# MySensors_D1_mini.net
KiCad netlist of a schematic drawn in EAGLE
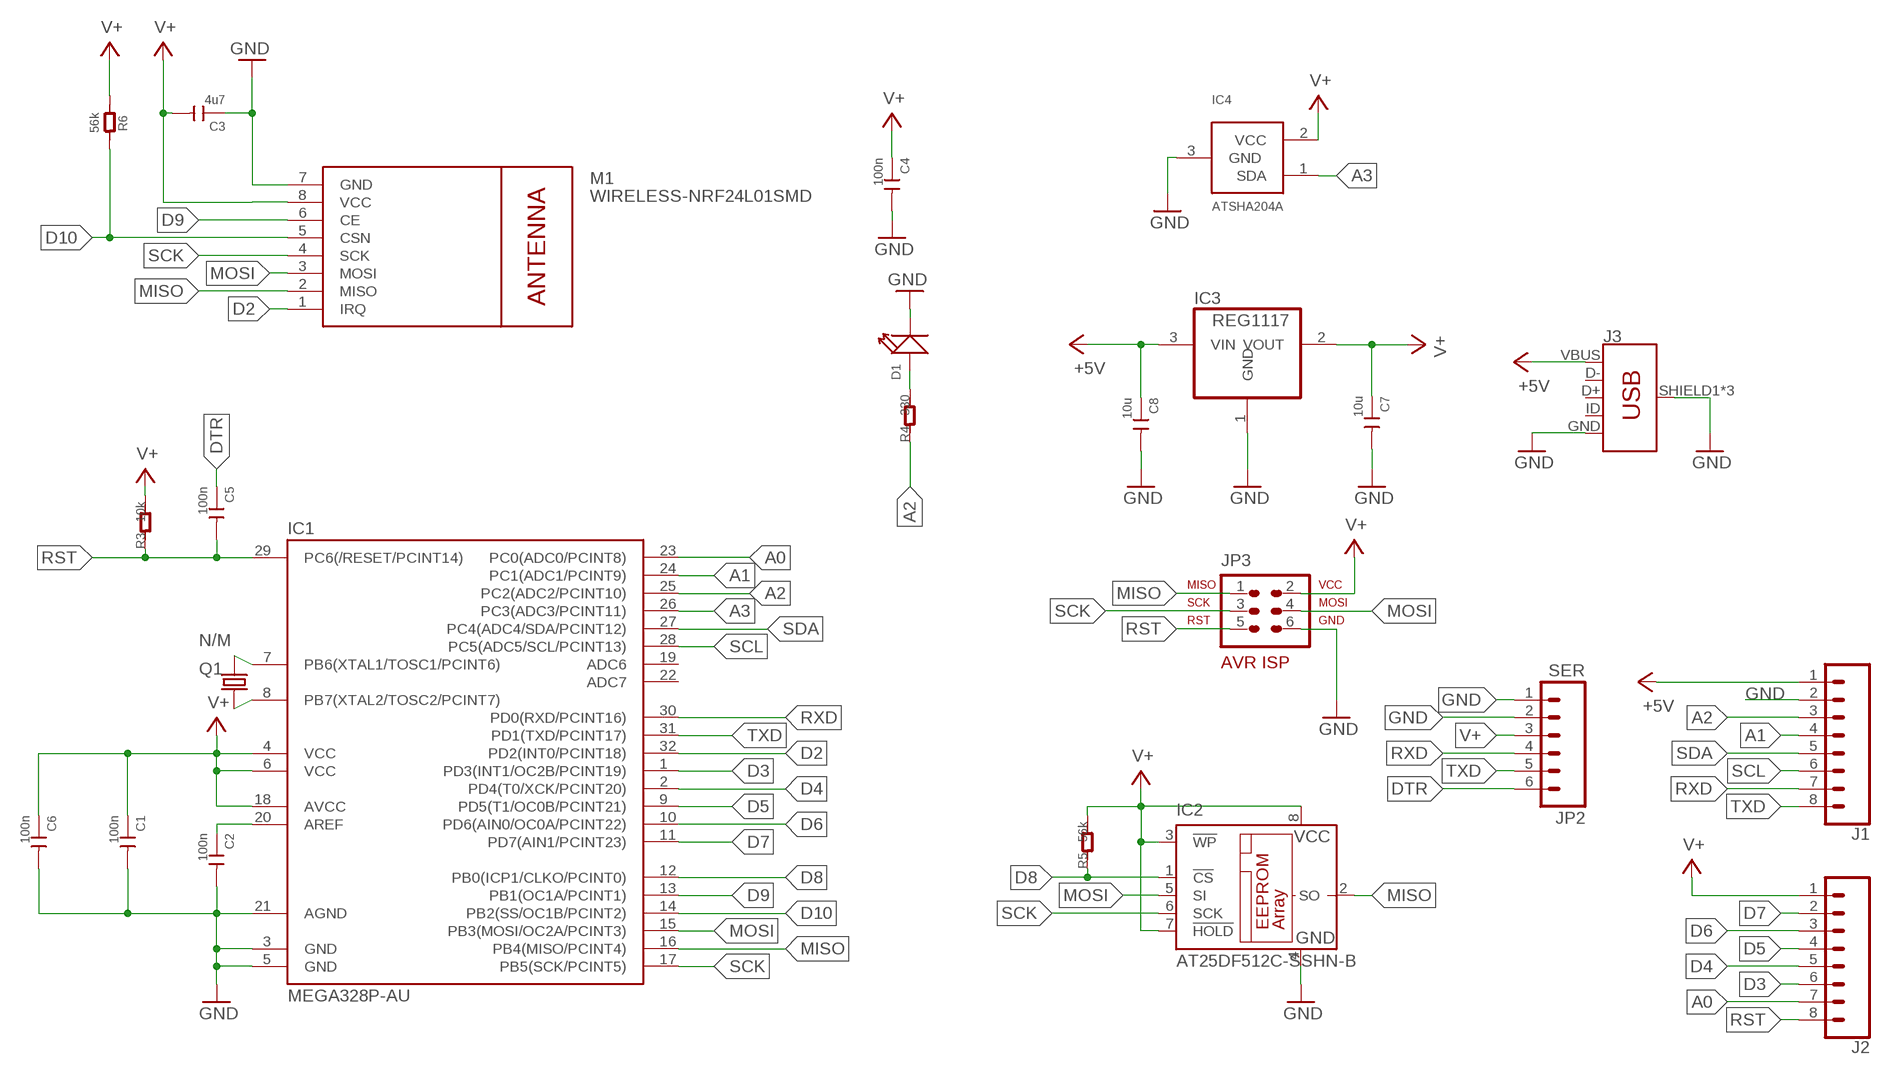
[diagram p0: schematic, sheet 1]

(export (version "E")
  (design (tool "Eeschema 10.0.6"))
  (components
    (comp (ref "C1")
      (value "100n")
      (footprint "eagle-import:C0402")
      (libsource (lib "eagle-import") (part "CAP-0402"))
    )
    (comp (ref "C2")
      (value "100n")
      (footprint "eagle-import:C0402")
      (libsource (lib "eagle-import") (part "CAP-0402"))
    )
    (comp (ref "C3")
      (value "4u7")
      (footprint "eagle-import:C0603")
      (libsource (lib "eagle-import") (part "CAP-0603"))
    )
    (comp (ref "C4")
      (value "100n")
      (footprint "eagle-import:C0402")
      (libsource (lib "eagle-import") (part "CAP-0402"))
    )
    (comp (ref "C5")
      (value "100n")
      (footprint "eagle-import:C0402")
      (libsource (lib "eagle-import") (part "CAP-0402"))
    )
    (comp (ref "C6")
      (value "100n")
      (footprint "eagle-import:C0402")
      (libsource (lib "eagle-import") (part "CAP-0402"))
    )
    (comp (ref "C7")
      (value "10u")
      (footprint "eagle-import:C1206")
      (libsource (lib "eagle-import") (part "CAP-1206"))
    )
    (comp (ref "C8")
      (value "10u")
      (footprint "eagle-import:C1206")
      (libsource (lib "eagle-import") (part "CAP-1206"))
    )
    (comp (ref "D1")
      (value "LED-0402")
      (footprint "eagle-import:LED-0402")
      (libsource (lib "eagle-import") (part "LED-0402"))
    )
    (comp (ref "IC1")
      (value "MEGA328P-AU")
      (footprint "eagle-import:TQFP32-08")
      (libsource (lib "eagle-import") (part "MEGA48/88/168-AU"))
    )
    (comp (ref "IC2")
      (value "AT25DF512C-SSHN-B")
      (footprint "eagle-import:SO-08")
      (fields (field (name "MF") "MICROCHIP") (field (name "MPN") "25AA080/SN"))
      (libsource (lib "eagle-import") (part "25SNAA080"))
    )
    (comp (ref "IC3")
      (value "REG1117")
      (footprint "eagle-import:SOT223")
      (libsource (lib "eagle-import") (part "REG1117"))
    )
    (comp (ref "IC4")
      (value "ATSHA204A")
      (footprint "eagle-import:SOT23")
      (libsource (lib "eagle-import") (part "ATSHA204A"))
    )
    (comp (ref "J1")
      (value "CONN_08\"")
      (footprint "eagle-import:1X08")
      (libsource (lib "eagle-import") (part "CONN_08{dblquote}"))
    )
    (comp (ref "J2")
      (value "CONN_08\"")
      (footprint "eagle-import:1X08")
      (libsource (lib "eagle-import") (part "CONN_08{dblquote}"))
    )
    (comp (ref "J3")
      (value "USB_MICRO-B_FEMALE-SMT")
      (footprint "eagle-import:USB-B-MICRO-SMD")
      (libsource (lib "eagle-import") (part "USB_MICRO-B_FEMALE-SMT"))
    )
    (comp (ref "JP2")
      (value "SER")
      (footprint "eagle-import:1X06_NO_SILK")
      (libsource (lib "eagle-import") (part "M06NO_SILK_FEMALE_PTH"))
    )
    (comp (ref "JP3")
      (value "N/M")
      (footprint "eagle-import:AVR-ISP-6")
      (libsource (lib "eagle-import") (part "AVR-ISP-6VERT"))
    )
    (comp (ref "M1")
      (value "WIRELESS-NRF24L01SMD")
      (footprint "eagle-import:WIRELESS-NRF24L01-SMD")
      (libsource (lib "eagle-import") (part "WIRELESS-NRF24L01SMD"))
    )
    (comp (ref "Q1")
      (value "N/M")
      (footprint "eagle-import:2P-L3.2XW1.5MM")
      (libsource (lib "eagle-import") (part "CRYSTAL-306010055"))
    )
    (comp (ref "R3")
      (value "10k")
      (footprint "eagle-import:R0402")
      (libsource (lib "eagle-import") (part "R-0402"))
    )
    (comp (ref "R4")
      (value "330")
      (footprint "eagle-import:R0402")
      (libsource (lib "eagle-import") (part "R-0402"))
    )
    (comp (ref "R5")
      (value "56k")
      (footprint "eagle-import:R0402")
      (libsource (lib "eagle-import") (part "R-0402"))
    )
    (comp (ref "R6")
      (value "56k")
      (footprint "eagle-import:R0402")
      (libsource (lib "eagle-import") (part "R-0402"))
    )
  )
  (nets
    (net (code "1") (name "+5V") (class "Default")
      (node (ref "C8") (pin "1") (pinfunction "1_1") (pintype "passive"))
      (node (ref "IC3") (pin "3") (pinfunction "VIN_3") (pintype "input"))
      (node (ref "J1") (pin "1") (pinfunction "1_1") (pintype "passive"))
      (node (ref "J3") (pin "VBUS") (pinfunction "VBUS_VBUS") (pintype "power_in"))
    )
    (net (code "2") (name "A0") (class "Default")
      (node (ref "IC1") (pin "23") (pinfunction "PC0(ADC0/PCINT8)_23") (pintype "bidirectional"))
      (node (ref "J2") (pin "7") (pinfunction "7_7") (pintype "passive"))
    )
    (net (code "3") (name "A1") (class "Default")
      (node (ref "IC1") (pin "24") (pinfunction "PC1(ADC1/PCINT9)_24") (pintype "bidirectional"))
      (node (ref "J1") (pin "4") (pinfunction "4_4") (pintype "passive"))
    )
    (net (code "4") (name "A2") (class "Default")
      (node (ref "IC1") (pin "25") (pinfunction "PC2(ADC2/PCINT10)_25") (pintype "bidirectional"))
      (node (ref "J1") (pin "3") (pinfunction "3_3") (pintype "passive"))
      (node (ref "R4") (pin "1") (pinfunction "1_1") (pintype "bidirectional"))
    )
    (net (code "5") (name "A3") (class "Default")
      (node (ref "IC1") (pin "26") (pinfunction "PC3(ADC3/PCINT11)_26") (pintype "bidirectional"))
      (node (ref "IC4") (pin "1") (pinfunction "SDA_1") (pintype "bidirectional"))
    )
    (net (code "6") (name "D2") (class "Default")
      (node (ref "IC1") (pin "32") (pinfunction "PD2(INT0/PCINT18)_32") (pintype "bidirectional"))
      (node (ref "M1") (pin "1") (pinfunction "IRQ_1") (pintype "bidirectional"))
    )
    (net (code "7") (name "D3") (class "Default")
      (node (ref "IC1") (pin "1") (pinfunction "PD3(INT1/OC2B/PCINT19)_1") (pintype "bidirectional"))
      (node (ref "J2") (pin "6") (pinfunction "6_6") (pintype "passive"))
    )
    (net (code "8") (name "D4") (class "Default")
      (node (ref "IC1") (pin "2") (pinfunction "PD4(T0/XCK/PCINT20)_2") (pintype "bidirectional"))
      (node (ref "J2") (pin "5") (pinfunction "5_5") (pintype "passive"))
    )
    (net (code "9") (name "D5") (class "Default")
      (node (ref "IC1") (pin "9") (pinfunction "PD5(T1/OC0B/PCINT21)_9") (pintype "bidirectional"))
      (node (ref "J2") (pin "4") (pinfunction "4_4") (pintype "passive"))
    )
    (net (code "10") (name "D6") (class "Default")
      (node (ref "IC1") (pin "10") (pinfunction "PD6(AIN0/OC0A/PCINT22)_10") (pintype "bidirectional"))
      (node (ref "J2") (pin "3") (pinfunction "3_3") (pintype "passive"))
    )
    (net (code "11") (name "D7") (class "Default")
      (node (ref "IC1") (pin "11") (pinfunction "PD7(AIN1/PCINT23)_11") (pintype "bidirectional"))
      (node (ref "J2") (pin "2") (pinfunction "2_2") (pintype "passive"))
    )
    (net (code "12") (name "D8") (class "Default")
      (node (ref "IC1") (pin "12") (pinfunction "PB0(ICP1/CLKO/PCINT0)_12") (pintype "bidirectional"))
      (node (ref "IC2") (pin "1") (pinfunction "~{CS}_1") (pintype "input"))
      (node (ref "R5") (pin "1") (pinfunction "1_1") (pintype "bidirectional"))
    )
    (net (code "13") (name "D9") (class "Default")
      (node (ref "IC1") (pin "13") (pinfunction "PB1(OC1A/PCINT1)_13") (pintype "bidirectional"))
      (node (ref "M1") (pin "6") (pinfunction "CE_6") (pintype "bidirectional"))
    )
    (net (code "14") (name "D10") (class "Default")
      (node (ref "IC1") (pin "14") (pinfunction "PB2(SS/OC1B/PCINT2)_14") (pintype "bidirectional"))
      (node (ref "M1") (pin "5") (pinfunction "CSN_5") (pintype "bidirectional"))
      (node (ref "R6") (pin "1") (pinfunction "1_1") (pintype "bidirectional"))
    )
    (net (code "15") (name "DTR") (class "Default")
      (node (ref "C5") (pin "1") (pinfunction "1_1") (pintype "passive"))
      (node (ref "JP2") (pin "6") (pinfunction "6_6") (pintype "passive"))
    )
    (net (code "16") (name "GND") (class "Default")
      (node (ref "C1") (pin "2") (pinfunction "2_2") (pintype "passive"))
      (node (ref "C2") (pin "2") (pinfunction "2_2") (pintype "passive"))
      (node (ref "C3") (pin "1") (pinfunction "1_1") (pintype "passive"))
      (node (ref "C4") (pin "2") (pinfunction "2_2") (pintype "passive"))
      (node (ref "C6") (pin "2") (pinfunction "2_2") (pintype "passive"))
      (node (ref "C7") (pin "2") (pinfunction "2_2") (pintype "passive"))
      (node (ref "C8") (pin "2") (pinfunction "2_2") (pintype "passive"))
      (node (ref "D1") (pin "-") (pinfunction "-_-") (pintype "passive"))
      (node (ref "IC1") (pin "21") (pinfunction "AGND_21") (pintype "power_in"))
      (node (ref "IC1") (pin "3") (pinfunction "GND_3") (pintype "power_in"))
      (node (ref "IC1") (pin "5") (pinfunction "GND_5") (pintype "power_in"))
      (node (ref "IC2") (pin "4") (pinfunction "GND_4") (pintype "power_in"))
      (node (ref "IC3") (pin "1") (pinfunction "GND_1") (pintype "power_in"))
      (node (ref "IC4") (pin "3") (pinfunction "GND_3") (pintype "bidirectional"))
      (node (ref "J1") (pin "2") (pinfunction "2_2") (pintype "passive"))
      (node (ref "J3") (pin "GND") (pinfunction "GND_GND") (pintype "power_in"))
      (node (ref "J3") (pin "SHIELD1") (pinfunction "SHIELD_SHIELD1") (pintype "bidirectional"))
      (node (ref "J3") (pin "SHIELD2") (pinfunction "SHIELD_SHIELD2") (pintype "bidirectional"))
      (node (ref "J3") (pin "SHIELD3") (pinfunction "SHIELD_SHIELD3") (pintype "bidirectional"))
      (node (ref "JP2") (pin "1") (pinfunction "1_1") (pintype "passive"))
      (node (ref "JP2") (pin "2") (pinfunction "2_2") (pintype "passive"))
      (node (ref "JP3") (pin "6") (pinfunction "6_6") (pintype "passive"))
      (node (ref "M1") (pin "7") (pinfunction "GND_7") (pintype "power_in"))
    )
    (net (code "17") (name "MISO") (class "Default")
      (node (ref "IC1") (pin "16") (pinfunction "PB4(MISO/PCINT4)_16") (pintype "bidirectional"))
      (node (ref "IC2") (pin "2") (pinfunction "SO_2") (pintype "bidirectional"))
      (node (ref "JP3") (pin "1") (pinfunction "1_1") (pintype "passive"))
      (node (ref "M1") (pin "2") (pinfunction "MISO_2") (pintype "bidirectional"))
    )
    (net (code "18") (name "MOSI") (class "Default")
      (node (ref "IC1") (pin "15") (pinfunction "PB3(MOSI/OC2A/PCINT3)_15") (pintype "bidirectional"))
      (node (ref "IC2") (pin "5") (pinfunction "SI_5") (pintype "input"))
      (node (ref "JP3") (pin "4") (pinfunction "4_4") (pintype "passive"))
      (node (ref "M1") (pin "3") (pinfunction "MOSI_3") (pintype "bidirectional"))
    )
    (net (code "19") (name "Net-(D1-Pad+)") (class "Default")
      (node (ref "D1") (pin "+") (pinfunction "+_+") (pintype "passive"))
      (node (ref "R4") (pin "2") (pinfunction "2_2") (pintype "bidirectional"))
    )
    (net (code "20") (name "Net-(IC1-AREF)") (class "Default")
      (node (ref "C2") (pin "1") (pinfunction "1_1") (pintype "passive"))
      (node (ref "IC1") (pin "20") (pinfunction "AREF_20") (pintype "passive"))
    )
    (net (code "21") (name "Net-(IC1-PB6(XTAL1{slash}TOSC1{slash}PCINT6))") (class "Default")
      (node (ref "IC1") (pin "7") (pinfunction "PB6(XTAL1/TOSC1/PCINT6)_7") (pintype "bidirectional"))
      (node (ref "Q1") (pin "1") (pinfunction "1_1") (pintype "passive"))
    )
    (net (code "22") (name "Net-(IC1-PB7(XTAL2{slash}TOSC2{slash}PCINT7))") (class "Default")
      (node (ref "IC1") (pin "8") (pinfunction "PB7(XTAL2/TOSC2/PCINT7)_8") (pintype "bidirectional"))
      (node (ref "Q1") (pin "2") (pinfunction "2_2") (pintype "passive"))
    )
    (net (code "23") (name "RST") (class "Default")
      (node (ref "C5") (pin "2") (pinfunction "2_2") (pintype "passive"))
      (node (ref "IC1") (pin "29") (pinfunction "PC6(/RESET/PCINT14)_29") (pintype "bidirectional"))
      (node (ref "J2") (pin "8") (pinfunction "8_8") (pintype "passive"))
      (node (ref "JP3") (pin "5") (pinfunction "5_5") (pintype "passive"))
      (node (ref "R3") (pin "1") (pinfunction "1_1") (pintype "bidirectional"))
    )
    (net (code "24") (name "RXD") (class "Default")
      (node (ref "IC1") (pin "30") (pinfunction "PD0(RXD/PCINT16)_30") (pintype "bidirectional"))
      (node (ref "J1") (pin "7") (pinfunction "7_7") (pintype "passive"))
      (node (ref "JP2") (pin "4") (pinfunction "4_4") (pintype "passive"))
    )
    (net (code "25") (name "SCK") (class "Default")
      (node (ref "IC1") (pin "17") (pinfunction "PB5(SCK/PCINT5)_17") (pintype "bidirectional"))
      (node (ref "IC2") (pin "6") (pinfunction "SCK_6") (pintype "input"))
      (node (ref "JP3") (pin "3") (pinfunction "3_3") (pintype "passive"))
      (node (ref "M1") (pin "4") (pinfunction "SCK_4") (pintype "bidirectional"))
    )
    (net (code "26") (name "SCL") (class "Default")
      (node (ref "IC1") (pin "28") (pinfunction "PC5(ADC5/SCL/PCINT13)_28") (pintype "bidirectional"))
      (node (ref "J1") (pin "6") (pinfunction "6_6") (pintype "passive"))
    )
    (net (code "27") (name "SDA") (class "Default")
      (node (ref "IC1") (pin "27") (pinfunction "PC4(ADC4/SDA/PCINT12)_27") (pintype "bidirectional"))
      (node (ref "J1") (pin "5") (pinfunction "5_5") (pintype "passive"))
    )
    (net (code "28") (name "TXD") (class "Default")
      (node (ref "IC1") (pin "31") (pinfunction "PD1(TXD/PCINT17)_31") (pintype "bidirectional"))
      (node (ref "J1") (pin "8") (pinfunction "8_8") (pintype "passive"))
      (node (ref "JP2") (pin "5") (pinfunction "5_5") (pintype "passive"))
    )
    (net (code "29") (name "V+") (class "Default")
      (node (ref "C1") (pin "1") (pinfunction "1_1") (pintype "passive"))
      (node (ref "C3") (pin "2") (pinfunction "2_2") (pintype "passive"))
      (node (ref "C4") (pin "1") (pinfunction "1_1") (pintype "passive"))
      (node (ref "C6") (pin "1") (pinfunction "1_1") (pintype "passive"))
      (node (ref "C7") (pin "1") (pinfunction "1_1") (pintype "passive"))
      (node (ref "IC1") (pin "18") (pinfunction "AVCC_18") (pintype "passive"))
      (node (ref "IC1") (pin "4") (pinfunction "VCC_4") (pintype "power_in"))
      (node (ref "IC1") (pin "6") (pinfunction "VCC_6") (pintype "power_in"))
      (node (ref "IC2") (pin "3") (pinfunction "~{WP}_3") (pintype "input"))
      (node (ref "IC2") (pin "7") (pinfunction "~{HOLD}_7") (pintype "input"))
      (node (ref "IC2") (pin "8") (pinfunction "VCC_8") (pintype "power_in"))
      (node (ref "IC3") (pin "2") (pinfunction "VOUT_2") (pintype "output"))
      (node (ref "IC4") (pin "2") (pinfunction "VCC_2") (pintype "bidirectional"))
      (node (ref "J2") (pin "1") (pinfunction "1_1") (pintype "passive"))
      (node (ref "JP2") (pin "3") (pinfunction "3_3") (pintype "passive"))
      (node (ref "JP3") (pin "2") (pinfunction "2_2") (pintype "passive"))
      (node (ref "M1") (pin "8") (pinfunction "VCC_8") (pintype "power_in"))
      (node (ref "R3") (pin "2") (pinfunction "2_2") (pintype "bidirectional"))
      (node (ref "R5") (pin "2") (pinfunction "2_2") (pintype "bidirectional"))
      (node (ref "R6") (pin "2") (pinfunction "2_2") (pintype "bidirectional"))
    )
    (net (code "30") (name "unconnected-(IC1-ADC6-Pad19)") (class "Default")
      (node (ref "IC1") (pin "19") (pinfunction "ADC6_19") (pintype "passive"))
    )
    (net (code "31") (name "unconnected-(IC1-ADC7-Pad22)") (class "Default")
      (node (ref "IC1") (pin "22") (pinfunction "ADC7_22") (pintype "passive"))
    )
    (net (code "32") (name "unconnected-(J3-PadD+)") (class "Default")
      (node (ref "J3") (pin "D+") (pinfunction "D+_D+") (pintype "bidirectional"))
    )
    (net (code "33") (name "unconnected-(J3-PadD-)") (class "Default")
      (node (ref "J3") (pin "D-") (pinfunction "D-_D-") (pintype "bidirectional"))
    )
    (net (code "34") (name "unconnected-(J3-PadID)") (class "Default")
      (node (ref "J3") (pin "ID") (pinfunction "ID_ID") (pintype "bidirectional"))
    )
  )
)
